# WallE.net
KiCad netlist of a schematic drawn in EAGLE
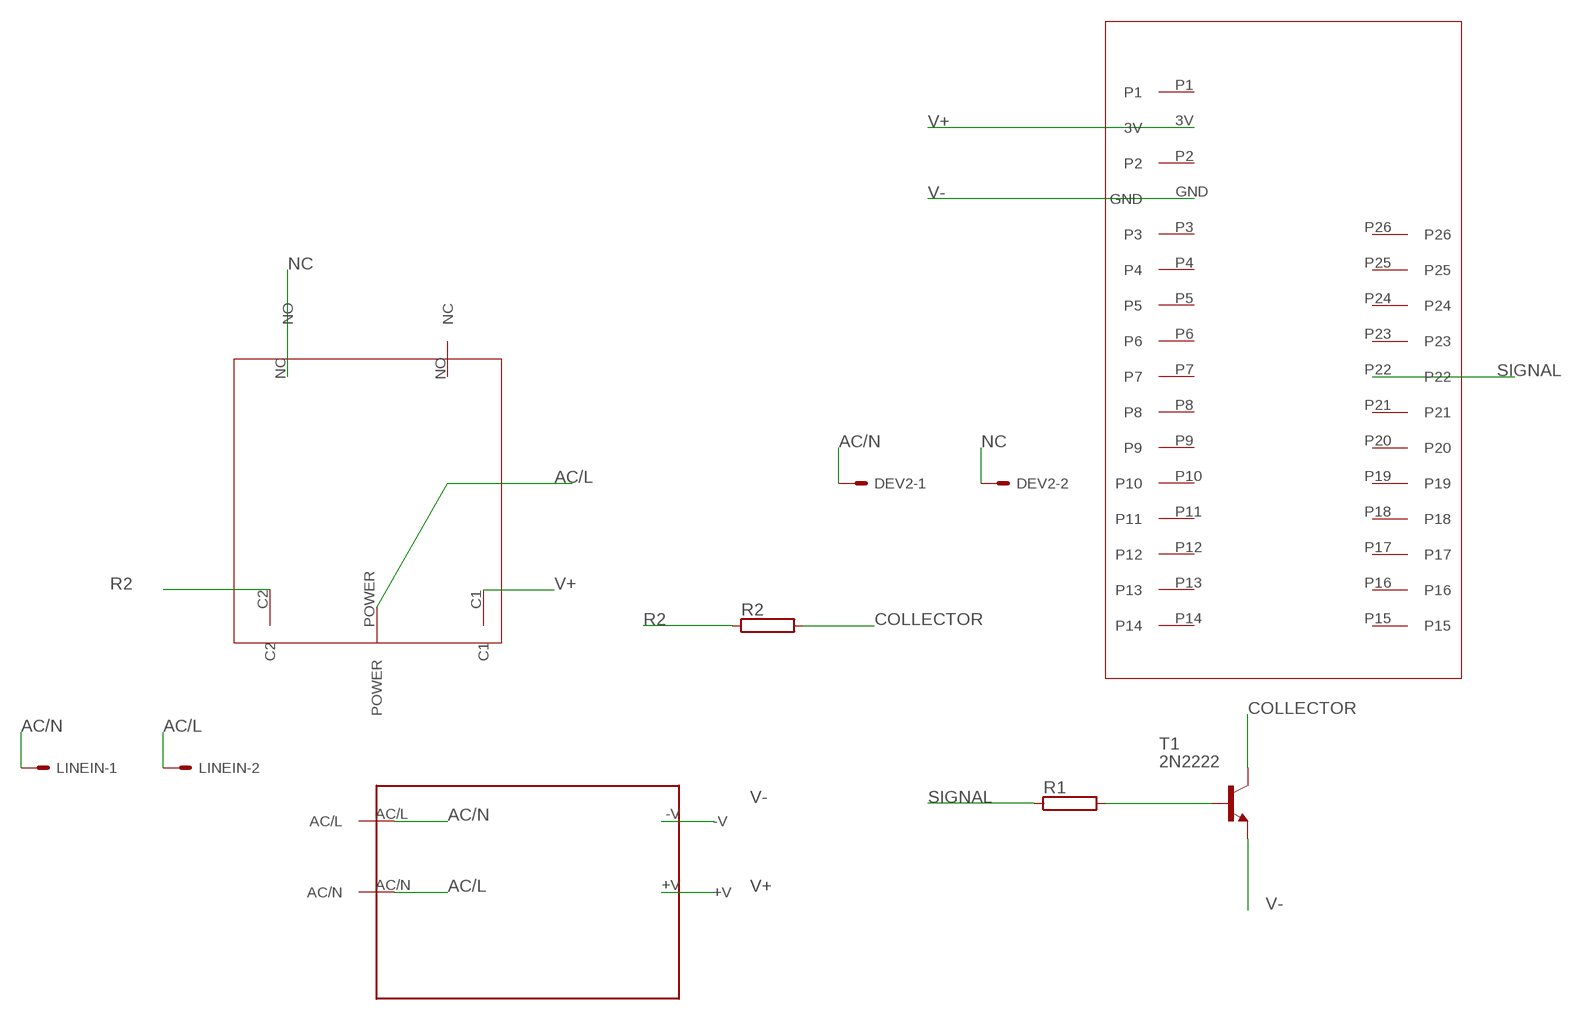
[diagram p0: schematic, sheet 1]

(export (version "E")
  (design (tool "Eeschema 10.0.6"))
  (components
    (comp (ref "DEV2")
      (value "dev1")
      (footprint "eagle-import:332-02")
      (libsource (lib "eagle-import") (part "332-02"))
    )
    (comp (ref "LINEIN")
      (value "AC/L")
      (footprint "eagle-import:332-02")
      (libsource (lib "eagle-import") (part "332-02"))
    )
    (comp (ref "R1")
      (value "RMG100-V")
      (footprint "eagle-import:TO-247-2V")
      (libsource (lib "eagle-import") (part "RMG100-V"))
    )
    (comp (ref "R2")
      (value "RMG100-V")
      (footprint "eagle-import:TO-247-2V")
      (libsource (lib "eagle-import") (part "RMG100-V"))
    )
    (comp (ref "T1")
      (value "2N2222")
      (footprint "eagle-import:TO18")
      (libsource (lib "eagle-import") (part "2N2222"))
    )
    (comp (ref "U$1")
      (value "POWER_COMPONENT")
      (footprint "eagle-import:POWER_COMPONENT")
      (libsource (lib "eagle-import") (part "POWER_COMPONENT"))
    )
    (comp (ref "U$2")
      (value "3VUXCELLCOIL")
      (footprint "eagle-import:3VUXCELLRELAY")
      (libsource (lib "eagle-import") (part "3VUXCELLCOIL"))
    )
    (comp (ref "U$3")
      (value "ESP8266")
      (footprint "eagle-import:ESP8266")
      (libsource (lib "eagle-import") (part "ESP8266"))
    )
  )
  (nets
    (net (code "1") (name "/AC{slash}L") (class "Default")
      (node (ref "LINEIN") (pin "2") (pinfunction "S_2") (pintype "passive"))
      (node (ref "U$1") (pin "AC/N") (pinfunction "AC/N_AC/N") (pintype "bidirectional"))
      (node (ref "U$2") (pin "POWER") (pinfunction "POWER_POWER") (pintype "bidirectional"))
    )
    (net (code "2") (name "/AC{slash}N") (class "Default")
      (node (ref "DEV2") (pin "1") (pinfunction "S_1") (pintype "passive"))
      (node (ref "LINEIN") (pin "1") (pinfunction "S_1") (pintype "passive"))
      (node (ref "U$1") (pin "AC/L") (pinfunction "AC/L_AC/L") (pintype "bidirectional"))
    )
    (net (code "3") (name "/COLLECTOR") (class "Default")
      (node (ref "R2") (pin "2") (pinfunction "2_2") (pintype "passive"))
      (node (ref "T1") (pin "3") (pinfunction "C_3") (pintype "passive"))
    )
    (net (code "4") (name "/NC") (class "Default")
      (node (ref "DEV2") (pin "2") (pinfunction "S_2") (pintype "passive"))
      (node (ref "U$2") (pin "NC") (pinfunction "NO_NC") (pintype "bidirectional"))
    )
    (net (code "5") (name "/R2") (class "Default")
      (node (ref "R2") (pin "1") (pinfunction "1_1") (pintype "passive"))
      (node (ref "U$2") (pin "C2") (pinfunction "C2_C2") (pintype "bidirectional"))
    )
    (net (code "6") (name "/SIGNAL") (class "Default")
      (node (ref "R1") (pin "1") (pinfunction "1_1") (pintype "passive"))
      (node (ref "U$3") (pin "P22") (pinfunction "P22_P22") (pintype "bidirectional"))
    )
    (net (code "7") (name "/V+") (class "Default")
      (node (ref "U$1") (pin "+V") (pinfunction "+V_+V") (pintype "bidirectional"))
      (node (ref "U$2") (pin "C1") (pinfunction "C1_C1") (pintype "bidirectional"))
      (node (ref "U$3") (pin "3V") (pinfunction "3V_3V") (pintype "bidirectional"))
    )
    (net (code "8") (name "/V-") (class "Default")
      (node (ref "T1") (pin "1") (pinfunction "E_1") (pintype "passive"))
      (node (ref "U$1") (pin "-V") (pinfunction "-V_-V") (pintype "bidirectional"))
      (node (ref "U$3") (pin "GND") (pinfunction "GND_GND") (pintype "bidirectional"))
    )
    (net (code "9") (name "Net-(T1-B)") (class "Default")
      (node (ref "R1") (pin "2") (pinfunction "2_2") (pintype "passive"))
      (node (ref "T1") (pin "2") (pinfunction "B_2") (pintype "passive"))
    )
    (net (code "10") (name "unconnected-(U$2-NC-PadNO)") (class "Default")
      (node (ref "U$2") (pin "NO") (pinfunction "NC_NO") (pintype "bidirectional"))
    )
    (net (code "11") (name "unconnected-(U$3-PadP1)") (class "Default")
      (node (ref "U$3") (pin "P1") (pinfunction "P1_P1") (pintype "bidirectional"))
    )
    (net (code "12") (name "unconnected-(U$3-PadP2)") (class "Default")
      (node (ref "U$3") (pin "P2") (pinfunction "P2_P2") (pintype "bidirectional"))
    )
    (net (code "13") (name "unconnected-(U$3-PadP3)") (class "Default")
      (node (ref "U$3") (pin "P3") (pinfunction "P3_P3") (pintype "bidirectional"))
    )
    (net (code "14") (name "unconnected-(U$3-PadP4)") (class "Default")
      (node (ref "U$3") (pin "P4") (pinfunction "P4_P4") (pintype "bidirectional"))
    )
    (net (code "15") (name "unconnected-(U$3-PadP5)") (class "Default")
      (node (ref "U$3") (pin "P5") (pinfunction "P5_P5") (pintype "bidirectional"))
    )
    (net (code "16") (name "unconnected-(U$3-PadP6)") (class "Default")
      (node (ref "U$3") (pin "P6") (pinfunction "P6_P6") (pintype "bidirectional"))
    )
    (net (code "17") (name "unconnected-(U$3-PadP7)") (class "Default")
      (node (ref "U$3") (pin "P7") (pinfunction "P7_P7") (pintype "bidirectional"))
    )
    (net (code "18") (name "unconnected-(U$3-PadP8)") (class "Default")
      (node (ref "U$3") (pin "P8") (pinfunction "P8_P8") (pintype "bidirectional"))
    )
    (net (code "19") (name "unconnected-(U$3-PadP9)") (class "Default")
      (node (ref "U$3") (pin "P9") (pinfunction "P9_P9") (pintype "bidirectional"))
    )
    (net (code "20") (name "unconnected-(U$3-PadP10)") (class "Default")
      (node (ref "U$3") (pin "P10") (pinfunction "P10_P10") (pintype "bidirectional"))
    )
    (net (code "21") (name "unconnected-(U$3-PadP11)") (class "Default")
      (node (ref "U$3") (pin "P11") (pinfunction "P11_P11") (pintype "bidirectional"))
    )
    (net (code "22") (name "unconnected-(U$3-PadP12)") (class "Default")
      (node (ref "U$3") (pin "P12") (pinfunction "P12_P12") (pintype "bidirectional"))
    )
    (net (code "23") (name "unconnected-(U$3-PadP13)") (class "Default")
      (node (ref "U$3") (pin "P13") (pinfunction "P13_P13") (pintype "bidirectional"))
    )
    (net (code "24") (name "unconnected-(U$3-PadP14)") (class "Default")
      (node (ref "U$3") (pin "P14") (pinfunction "P14_P14") (pintype "bidirectional"))
    )
    (net (code "25") (name "unconnected-(U$3-PadP15)") (class "Default")
      (node (ref "U$3") (pin "P15") (pinfunction "P15_P15") (pintype "bidirectional"))
    )
    (net (code "26") (name "unconnected-(U$3-PadP16)") (class "Default")
      (node (ref "U$3") (pin "P16") (pinfunction "P16_P16") (pintype "bidirectional"))
    )
    (net (code "27") (name "unconnected-(U$3-PadP17)") (class "Default")
      (node (ref "U$3") (pin "P17") (pinfunction "P17_P17") (pintype "bidirectional"))
    )
    (net (code "28") (name "unconnected-(U$3-PadP18)") (class "Default")
      (node (ref "U$3") (pin "P18") (pinfunction "P18_P18") (pintype "bidirectional"))
    )
    (net (code "29") (name "unconnected-(U$3-PadP19)") (class "Default")
      (node (ref "U$3") (pin "P19") (pinfunction "P19_P19") (pintype "bidirectional"))
    )
    (net (code "30") (name "unconnected-(U$3-PadP20)") (class "Default")
      (node (ref "U$3") (pin "P20") (pinfunction "P20_P20") (pintype "bidirectional"))
    )
    (net (code "31") (name "unconnected-(U$3-PadP21)") (class "Default")
      (node (ref "U$3") (pin "P21") (pinfunction "P21_P21") (pintype "bidirectional"))
    )
    (net (code "32") (name "unconnected-(U$3-PadP23)") (class "Default")
      (node (ref "U$3") (pin "P23") (pinfunction "P23_P23") (pintype "bidirectional"))
    )
    (net (code "33") (name "unconnected-(U$3-PadP24)") (class "Default")
      (node (ref "U$3") (pin "P24") (pinfunction "P24_P24") (pintype "bidirectional"))
    )
    (net (code "34") (name "unconnected-(U$3-PadP25)") (class "Default")
      (node (ref "U$3") (pin "P25") (pinfunction "P25_P25") (pintype "bidirectional"))
    )
    (net (code "35") (name "unconnected-(U$3-PadP26)") (class "Default")
      (node (ref "U$3") (pin "P26") (pinfunction "P26_P26") (pintype "bidirectional"))
    )
  )
)
